# DC_DC_12V.net
KiCad netlist of a schematic drawn in Altium Designer
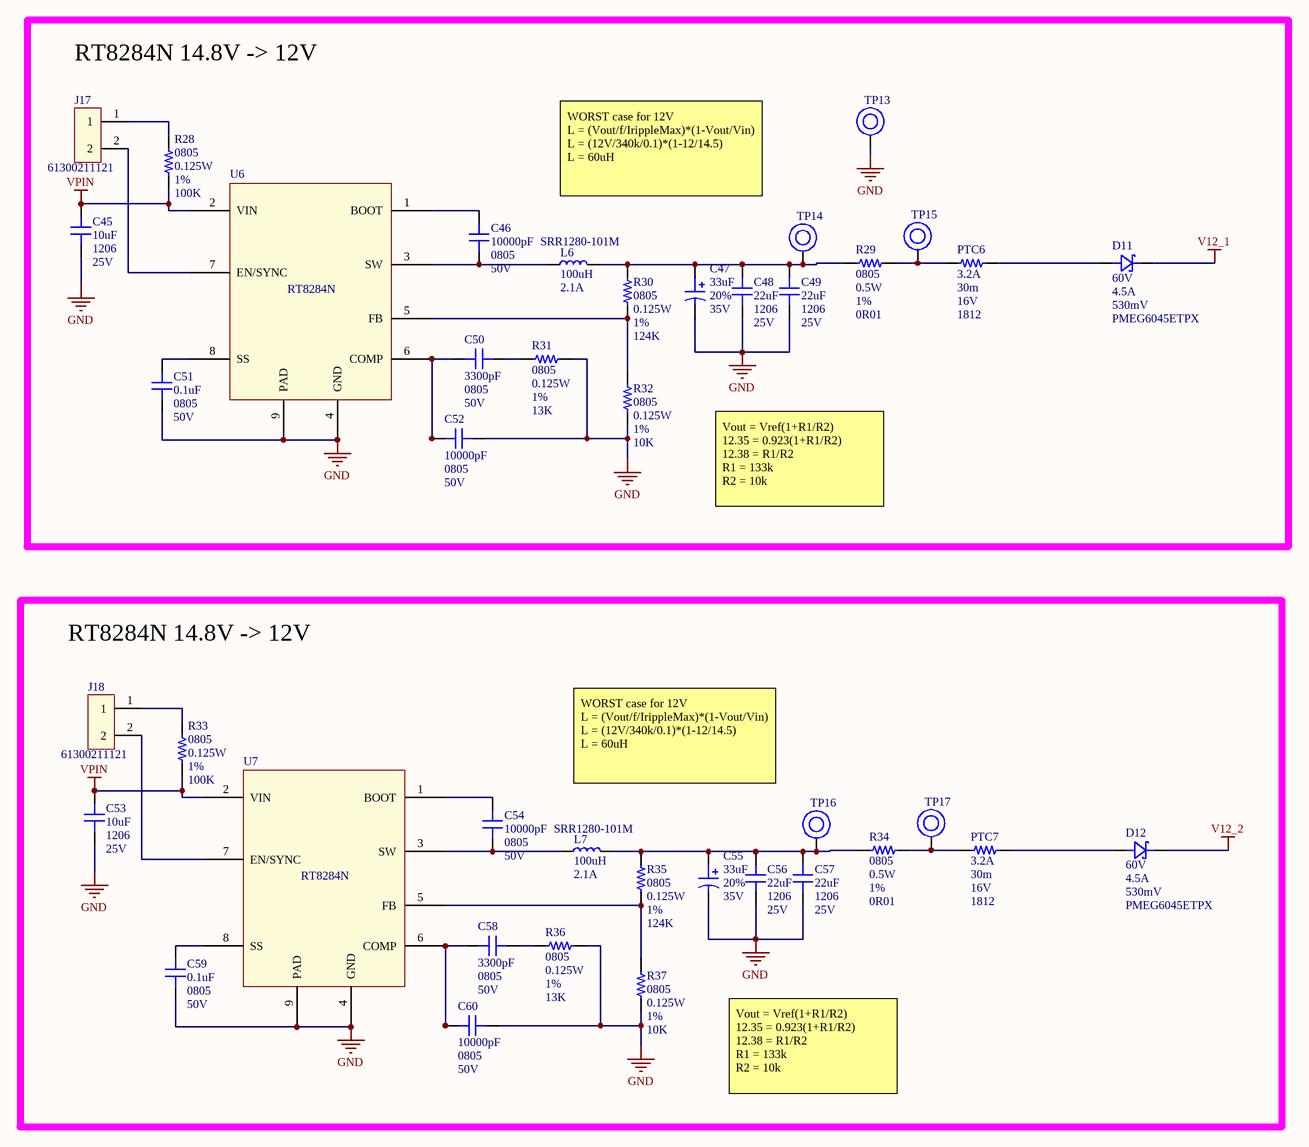
[diagram p0: DC_DC_12V.SchDoc]

(export (version "E")
  (design (tool "Eeschema 10.0.6"))
  (components
    (comp (ref "C45")
      (value "10uF")
      (footprint "CAP_1206")
      (description "CAP CER 10uF 25V 1206")
      (fields
        (field (name "PART NUMBER") "CL31A106KAHNFNE‎")
        (field (name "PACKAGE") "1206")
        (field (name "VOLTAGE") "25V")
        (field (name "Comment") "CAP_‎CL31A106KAHNFNE‎")
      )
      (libsource (lib "SecureBot") (part "CAP_‎CL31A106KAHNFNE‎"))
    )
    (comp (ref "C46")
      (value "10000pF")
      (footprint "CAP_0805")
      (description "CAP CER 10000pF 50V 0805")
      (fields
        (field (name "PART NUMBER") "‎CL21B103KBANNNC")
        (field (name "PACKAGE") "0805")
        (field (name "VOLTAGE") "50V")
        (field (name "Comment") "CAP_‎‎‎‎CL21B103KBANNNC")
      )
      (libsource (lib "SecureBot") (part "CAP_‎‎‎‎CL21B103KBANNNC"))
    )
    (comp (ref "C47")
      (value "33uF")
      (footprint "CAP ALU - 6.3mm DIA")
      (description "CAP ALU 33µF 35V")
      (fields
        (field (name "PART NUMBER") "EEE-FK1V330P")
        (field (name "TOLERANCE") "20%")
        (field (name "VOLTAGE") "35V")
        (field (name "Comment") "CAP_EEE-FK1V330P")
      )
      (libsource (lib "SecureBot") (part "CAP_EEE-FK1V330P"))
    )
    (comp (ref "C48")
      (value "22uF")
      (footprint "CAP_1206")
      (description "CAP CER 22uF 25V 1206")
      (fields
        (field (name "PART NUMBER") "CL31A226KAHNNNE‎")
        (field (name "PACKAGE") "1206")
        (field (name "VOLTAGE") "25V")
        (field (name "Comment") "CAP_‎‎CL31A226KAHNNNE‎")
      )
      (libsource (lib "SecureBot") (part "CAP_‎‎CL31A226KAHNNNE‎"))
    )
    (comp (ref "C49")
      (value "22uF")
      (footprint "CAP_1206")
      (description "CAP CER 22uF 25V 1206")
      (fields
        (field (name "PART NUMBER") "CL31A226KAHNNNE‎")
        (field (name "PACKAGE") "1206")
        (field (name "VOLTAGE") "25V")
        (field (name "Comment") "CAP_‎‎CL31A226KAHNNNE‎")
      )
      (libsource (lib "SecureBot") (part "CAP_‎‎CL31A226KAHNNNE‎"))
    )
    (comp (ref "C50")
      (value "3300pF")
      (footprint "CAP_0805")
      (description "CAP CER 3300pF 50V 0805")
      (fields
        (field (name "PART NUMBER") "CL21B332KBANNNC‎")
        (field (name "PACKAGE") "0805")
        (field (name "VOLTAGE") "50V")
        (field (name "Comment") "CAP_CL21B332KBANNNC‎")
      )
      (libsource (lib "SecureBot") (part "CAP_CL21B332KBANNNC‎"))
    )
    (comp (ref "C51")
      (value "0.1uF")
      (footprint "CAP_0805")
      (description "CAP CER 0.1uF 50V 0805")
      (fields
        (field (name "PART NUMBER") "CC0805KRX7R9BB104‎")
        (field (name "PACKAGE") "0805")
        (field (name "VOLTAGE") "50V")
        (field (name "Comment") "CAP_CC0805KRX7R9BB104‎")
      )
      (libsource (lib "SecureBot") (part "CAP_CC0805KRX7R9BB104‎"))
    )
    (comp (ref "C52")
      (value "10000pF")
      (footprint "CAP_0805")
      (description "CAP CER 10000pF 50V 0805")
      (fields
        (field (name "PART NUMBER") "‎CL21B103KBANNNC")
        (field (name "PACKAGE") "0805")
        (field (name "VOLTAGE") "50V")
        (field (name "Comment") "CAP_‎‎‎‎CL21B103KBANNNC")
      )
      (libsource (lib "SecureBot") (part "CAP_‎‎‎‎CL21B103KBANNNC"))
    )
    (comp (ref "C53")
      (value "10uF")
      (footprint "CAP_1206")
      (description "CAP CER 10uF 25V 1206")
      (fields
        (field (name "PART NUMBER") "CL31A106KAHNFNE‎")
        (field (name "PACKAGE") "1206")
        (field (name "VOLTAGE") "25V")
        (field (name "Comment") "CAP_‎CL31A106KAHNFNE‎")
      )
      (libsource (lib "SecureBot") (part "CAP_‎CL31A106KAHNFNE‎"))
    )
    (comp (ref "C54")
      (value "10000pF")
      (footprint "CAP_0805")
      (description "CAP CER 10000pF 50V 0805")
      (fields
        (field (name "PART NUMBER") "‎CL21B103KBANNNC")
        (field (name "PACKAGE") "0805")
        (field (name "VOLTAGE") "50V")
        (field (name "Comment") "CAP_‎‎‎‎CL21B103KBANNNC")
      )
      (libsource (lib "SecureBot") (part "CAP_‎‎‎‎CL21B103KBANNNC"))
    )
    (comp (ref "C55")
      (value "33uF")
      (footprint "CAP ALU - 6.3mm DIA")
      (description "CAP ALU 33µF 35V")
      (fields
        (field (name "PART NUMBER") "EEE-FK1V330P")
        (field (name "TOLERANCE") "20%")
        (field (name "VOLTAGE") "35V")
        (field (name "Comment") "CAP_EEE-FK1V330P")
      )
      (libsource (lib "SecureBot") (part "CAP_EEE-FK1V330P"))
    )
    (comp (ref "C56")
      (value "22uF")
      (footprint "CAP_1206")
      (description "CAP CER 22uF 25V 1206")
      (fields
        (field (name "PART NUMBER") "CL31A226KAHNNNE‎")
        (field (name "PACKAGE") "1206")
        (field (name "VOLTAGE") "25V")
        (field (name "Comment") "CAP_‎‎CL31A226KAHNNNE‎")
      )
      (libsource (lib "SecureBot") (part "CAP_‎‎CL31A226KAHNNNE‎"))
    )
    (comp (ref "C57")
      (value "22uF")
      (footprint "CAP_1206")
      (description "CAP CER 22uF 25V 1206")
      (fields
        (field (name "PART NUMBER") "CL31A226KAHNNNE‎")
        (field (name "PACKAGE") "1206")
        (field (name "VOLTAGE") "25V")
        (field (name "Comment") "CAP_‎‎CL31A226KAHNNNE‎")
      )
      (libsource (lib "SecureBot") (part "CAP_‎‎CL31A226KAHNNNE‎"))
    )
    (comp (ref "C58")
      (value "3300pF")
      (footprint "CAP_0805")
      (description "CAP CER 3300pF 50V 0805")
      (fields
        (field (name "PART NUMBER") "CL21B332KBANNNC‎")
        (field (name "PACKAGE") "0805")
        (field (name "VOLTAGE") "50V")
        (field (name "Comment") "CAP_CL21B332KBANNNC‎")
      )
      (libsource (lib "SecureBot") (part "CAP_CL21B332KBANNNC‎"))
    )
    (comp (ref "C59")
      (value "0.1uF")
      (footprint "CAP_0805")
      (description "CAP CER 0.1uF 50V 0805")
      (fields
        (field (name "PART NUMBER") "CC0805KRX7R9BB104‎")
        (field (name "PACKAGE") "0805")
        (field (name "VOLTAGE") "50V")
        (field (name "Comment") "CAP_CC0805KRX7R9BB104‎")
      )
      (libsource (lib "SecureBot") (part "CAP_CC0805KRX7R9BB104‎"))
    )
    (comp (ref "C60")
      (value "10000pF")
      (footprint "CAP_0805")
      (description "CAP CER 10000pF 50V 0805")
      (fields
        (field (name "PART NUMBER") "‎CL21B103KBANNNC")
        (field (name "PACKAGE") "0805")
        (field (name "VOLTAGE") "50V")
        (field (name "Comment") "CAP_‎‎‎‎CL21B103KBANNNC")
      )
      (libsource (lib "SecureBot") (part "CAP_‎‎‎‎CL21B103KBANNNC"))
    )
    (comp (ref "D11")
      (value "DIODE_SCH_PMEG6045ETPX")
      (footprint "DO-214AC_SOD128")
      (description "Diode Schottky 60V 4.5A Surface Mount CFP5")
      (fields
        (field (name "VOLTAGE") "60V")
        (field (name "CURRENT") "4.5A")
        (field (name "VF") "530mV")
        (field (name "PART NUMBER") "PMEG6045ETPX")
      )
      (libsource (lib "SecureBot") (part "DIODE_SCH_PMEG6045ETPX"))
    )
    (comp (ref "D12")
      (value "DIODE_SCH_PMEG6045ETPX")
      (footprint "DO-214AC_SOD128")
      (description "Diode Schottky 60V 4.5A Surface Mount CFP5")
      (fields
        (field (name "VOLTAGE") "60V")
        (field (name "CURRENT") "4.5A")
        (field (name "VF") "530mV")
        (field (name "PART NUMBER") "PMEG6045ETPX")
      )
      (libsource (lib "SecureBot") (part "DIODE_SCH_PMEG6045ETPX"))
    )
    (comp (ref "J17")
      (value "Header 2 pin SM")
      (footprint "HDR1X2")
      (fields (field (name "PART NUMBER") "61300211121"))
      (libsource (lib "SecureBot") (part "Header 2 pin SM"))
    )
    (comp (ref "J18")
      (value "Header 2 pin SM")
      (footprint "HDR1X2")
      (fields (field (name "PART NUMBER") "61300211121"))
      (libsource (lib "SecureBot") (part "Header 2 pin SM"))
    )
    (comp (ref "L6")
      (value "100uH")
      (footprint "BOURNS 12.5x12.5mm")
      (description "IND 100µH Shielded Wirewound Inductor 2.1A")
      (fields
        (field (name "TOLERANCE") "20%")
        (field (name "CURRENT") "2.1A")
        (field (name "PART NUMBER") "SRR1280-101M")
        (field (name "Comment") "IND_SRR1280-101M")
      )
      (libsource (lib "SecureBot") (part "IND_SRR1280-101M"))
    )
    (comp (ref "L7")
      (value "100uH")
      (footprint "BOURNS 12.5x12.5mm")
      (description "IND 100µH Shielded Wirewound Inductor 2.1A")
      (fields
        (field (name "TOLERANCE") "20%")
        (field (name "CURRENT") "2.1A")
        (field (name "PART NUMBER") "SRR1280-101M")
        (field (name "Comment") "IND_SRR1280-101M")
      )
      (libsource (lib "SecureBot") (part "IND_SRR1280-101M"))
    )
    (comp (ref "PTC6")
      (value "PTC_0ZCG0160BF2C")
      (footprint "PTC - 1812")
      (description "PTC_Polymeric PTC Resettable Fuse 16V 1.6A Ih")
      (fields
        (field (name "PART NUMBER") "0ZCG0160BF2C")
        (field (name "TRIP VALUE") "3.2A")
        (field (name "RES") "30m")
        (field (name "VOLTAGE") "16V")
        (field (name "PACKAGE") "1812")
      )
      (libsource (lib "SecureBot") (part "PTC_0ZCG0160BF2C"))
    )
    (comp (ref "PTC7")
      (value "PTC_0ZCG0160BF2C")
      (footprint "PTC - 1812")
      (description "PTC_Polymeric PTC Resettable Fuse 16V 1.6A Ih")
      (fields
        (field (name "PART NUMBER") "0ZCG0160BF2C")
        (field (name "TRIP VALUE") "3.2A")
        (field (name "RES") "30m")
        (field (name "VOLTAGE") "16V")
        (field (name "PACKAGE") "1812")
      )
      (libsource (lib "SecureBot") (part "PTC_0ZCG0160BF2C"))
    )
    (comp (ref "R28")
      (value "100K")
      (footprint "RES_0805")
      (description "RES 100K 1% 1/8W 0805")
      (fields
        (field (name "PART NUMBER") "‎RMCF0805FT100K‎")
        (field (name "PACKAGE") "0805")
        (field (name "POWER") "0.125W")
        (field (name "TOLERANCE") "1%")
        (field (name "Comment") "RES_‎RMCF0805FT100K‎")
      )
      (libsource (lib "SecureBot") (part "RES_‎RMCF0805FT100K‎"))
    )
    (comp (ref "R29")
      (value "0R01")
      (footprint "RES_0805")
      (description "RES 0.01R 1% 1/2W 0805")
      (fields
        (field (name "PART NUMBER") "KRL1220E-M-R010-F-T5")
        (field (name "PACKAGE") "0805")
        (field (name "POWER") "0.5W")
        (field (name "TOLERANCE") "1%")
        (field (name "Comment") "RES_‎‎‎‎‎ KRL1220E-M-R010-F-T5")
      )
      (libsource (lib "SecureBot") (part "RES_‎‎‎‎‎ KRL1220E-M-R010-F-T5"))
    )
    (comp (ref "R30")
      (value "124K")
      (footprint "RES_0805")
      (description "RES 124K 1% 1/8W 0805")
      (fields
        (field (name "PART NUMBER") "RMCF0805FT124K")
        (field (name "PACKAGE") "0805")
        (field (name "POWER") "0.125W")
        (field (name "TOLERANCE") "1%")
        (field (name "Comment") "RES_‎RMCF0805FT124K")
      )
      (libsource (lib "SecureBot") (part "RES_‎RMCF0805FT124K"))
    )
    (comp (ref "R31")
      (value "13K")
      (footprint "RES_0805")
      (description "RES 13K 1% 1/8W 0805")
      (fields
        (field (name "PART NUMBER") "RC0805FR-0713KL")
        (field (name "PACKAGE") "0805")
        (field (name "POWER") "0.125W")
        (field (name "TOLERANCE") "1%")
        (field (name "Comment") "RES_‎ RC0805FR-0713KL")
      )
      (libsource (lib "SecureBot") (part "RES_‎ RC0805FR-0713KL"))
    )
    (comp (ref "R32")
      (value "10K")
      (footprint "RES_0805")
      (description "RES 10K 1% 1/8W 0805")
      (fields
        (field (name "PART NUMBER") "RMCF0805FT10K0")
        (field (name "PACKAGE") "0805")
        (field (name "POWER") "0.125W")
        (field (name "TOLERANCE") "1%")
        (field (name "Comment") "RES_‎RMCF0805FT10K0")
      )
      (libsource (lib "SecureBot") (part "RES_‎RMCF0805FT10K0"))
    )
    (comp (ref "R33")
      (value "100K")
      (footprint "RES_0805")
      (description "RES 100K 1% 1/8W 0805")
      (fields
        (field (name "PART NUMBER") "‎RMCF0805FT100K‎")
        (field (name "PACKAGE") "0805")
        (field (name "POWER") "0.125W")
        (field (name "TOLERANCE") "1%")
        (field (name "Comment") "RES_‎RMCF0805FT100K‎")
      )
      (libsource (lib "SecureBot") (part "RES_‎RMCF0805FT100K‎"))
    )
    (comp (ref "R34")
      (value "0R01")
      (footprint "RES_0805")
      (description "RES 0.01R 1% 1/2W 0805")
      (fields
        (field (name "PART NUMBER") "KRL1220E-M-R010-F-T5")
        (field (name "PACKAGE") "0805")
        (field (name "POWER") "0.5W")
        (field (name "TOLERANCE") "1%")
        (field (name "Comment") "RES_‎‎‎‎‎ KRL1220E-M-R010-F-T5")
      )
      (libsource (lib "SecureBot") (part "RES_‎‎‎‎‎ KRL1220E-M-R010-F-T5"))
    )
    (comp (ref "R35")
      (value "124K")
      (footprint "RES_0805")
      (description "RES 124K 1% 1/8W 0805")
      (fields
        (field (name "PART NUMBER") "RMCF0805FT124K")
        (field (name "PACKAGE") "0805")
        (field (name "POWER") "0.125W")
        (field (name "TOLERANCE") "1%")
        (field (name "Comment") "RES_‎RMCF0805FT124K")
      )
      (libsource (lib "SecureBot") (part "RES_‎RMCF0805FT124K"))
    )
    (comp (ref "R36")
      (value "13K")
      (footprint "RES_0805")
      (description "RES 13K 1% 1/8W 0805")
      (fields
        (field (name "PART NUMBER") "RC0805FR-0713KL")
        (field (name "PACKAGE") "0805")
        (field (name "POWER") "0.125W")
        (field (name "TOLERANCE") "1%")
        (field (name "Comment") "RES_‎ RC0805FR-0713KL")
      )
      (libsource (lib "SecureBot") (part "RES_‎ RC0805FR-0713KL"))
    )
    (comp (ref "R37")
      (value "10K")
      (footprint "RES_0805")
      (description "RES 10K 1% 1/8W 0805")
      (fields
        (field (name "PART NUMBER") "RMCF0805FT10K0")
        (field (name "PACKAGE") "0805")
        (field (name "POWER") "0.125W")
        (field (name "TOLERANCE") "1%")
        (field (name "Comment") "RES_‎RMCF0805FT10K0")
      )
      (libsource (lib "SecureBot") (part "RES_‎RMCF0805FT10K0"))
    )
    (comp (ref "TP13")
      (value "TestPoint 3x3mm")
      (footprint "TestPoint 3X3mm")
      (libsource (lib "SecureBot") (part "TestPoint 3x3mm"))
    )
    (comp (ref "TP14")
      (value "TestPoint 3x3mm")
      (footprint "TestPoint 3X3mm")
      (libsource (lib "SecureBot") (part "TestPoint 3x3mm"))
    )
    (comp (ref "TP15")
      (value "TestPoint 3x3mm")
      (footprint "TestPoint 3X3mm")
      (libsource (lib "SecureBot") (part "TestPoint 3x3mm"))
    )
    (comp (ref "TP16")
      (value "TestPoint 3x3mm")
      (footprint "TestPoint 3X3mm")
      (libsource (lib "SecureBot") (part "TestPoint 3x3mm"))
    )
    (comp (ref "TP17")
      (value "TestPoint 3x3mm")
      (footprint "TestPoint 3X3mm")
      (libsource (lib "SecureBot") (part "TestPoint 3x3mm"))
    )
    (comp (ref "U6")
      (value "REG_SW_RT8284N")
      (footprint "SOP8")
      (description "REG 2A, 23V, 340kHz Synchronous Step-Down Converter")
      (fields (field (name "PART NUMBER") "RT8284N"))
      (libsource (lib "SecureBot") (part "REG_SW_RT8284N"))
    )
    (comp (ref "U7")
      (value "REG_SW_RT8284N")
      (footprint "SOP8")
      (description "REG 2A, 23V, 340kHz Synchronous Step-Down Converter")
      (fields (field (name "PART NUMBER") "RT8284N"))
      (libsource (lib "SecureBot") (part "REG_SW_RT8284N"))
    )
  )
  (nets
    (net (code "1") (name "GND") (class "Default")
      (node (ref "C45") (pin "2") (pinfunction "2_2") (pintype "passive"))
      (node (ref "C47") (pin "2") (pinfunction "2_2") (pintype "passive"))
      (node (ref "C48") (pin "2") (pinfunction "2_2") (pintype "passive"))
      (node (ref "C49") (pin "2") (pinfunction "2_2") (pintype "passive"))
      (node (ref "C51") (pin "2") (pinfunction "2_2") (pintype "passive"))
      (node (ref "C52") (pin "2") (pinfunction "2_2") (pintype "passive"))
      (node (ref "C53") (pin "2") (pinfunction "2_2") (pintype "passive"))
      (node (ref "C55") (pin "2") (pinfunction "2_2") (pintype "passive"))
      (node (ref "C56") (pin "2") (pinfunction "2_2") (pintype "passive"))
      (node (ref "C57") (pin "2") (pinfunction "2_2") (pintype "passive"))
      (node (ref "C59") (pin "2") (pinfunction "2_2") (pintype "passive"))
      (node (ref "C60") (pin "2") (pinfunction "2_2") (pintype "passive"))
      (node (ref "R31") (pin "1") (pinfunction "1_1") (pintype "passive"))
      (node (ref "R32") (pin "2") (pinfunction "2_2") (pintype "passive"))
      (node (ref "R36") (pin "1") (pinfunction "1_1") (pintype "passive"))
      (node (ref "R37") (pin "2") (pinfunction "2_2") (pintype "passive"))
      (node (ref "TP13") (pin "1") (pinfunction "1_1") (pintype "passive"))
      (node (ref "U6") (pin "4") (pinfunction "GND_4") (pintype "passive"))
      (node (ref "U6") (pin "9") (pinfunction "PAD_9") (pintype "passive"))
      (node (ref "U7") (pin "4") (pinfunction "GND_4") (pintype "passive"))
      (node (ref "U7") (pin "9") (pinfunction "PAD_9") (pintype "passive"))
    )
    (net (code "2") (name "Net-(C47-Pad1)") (class "Default")
      (node (ref "C47") (pin "1") (pinfunction "1_1") (pintype "passive"))
      (node (ref "C48") (pin "1") (pinfunction "1_1") (pintype "passive"))
      (node (ref "C49") (pin "1") (pinfunction "1_1") (pintype "passive"))
      (node (ref "L6") (pin "2") (pinfunction "2_2") (pintype "passive"))
      (node (ref "R29") (pin "1") (pinfunction "1_1") (pintype "passive"))
      (node (ref "R30") (pin "1") (pinfunction "1_1") (pintype "passive"))
      (node (ref "TP14") (pin "1") (pinfunction "1_1") (pintype "passive"))
    )
    (net (code "3") (name "Net-(C50-Pad2)") (class "Default")
      (node (ref "C50") (pin "2") (pinfunction "2_2") (pintype "passive"))
      (node (ref "R31") (pin "2") (pinfunction "2_2") (pintype "passive"))
    )
    (net (code "4") (name "Net-(C55-Pad1)") (class "Default")
      (node (ref "C55") (pin "1") (pinfunction "1_1") (pintype "passive"))
      (node (ref "C56") (pin "1") (pinfunction "1_1") (pintype "passive"))
      (node (ref "C57") (pin "1") (pinfunction "1_1") (pintype "passive"))
      (node (ref "L7") (pin "2") (pinfunction "2_2") (pintype "passive"))
      (node (ref "R34") (pin "1") (pinfunction "1_1") (pintype "passive"))
      (node (ref "R35") (pin "1") (pinfunction "1_1") (pintype "passive"))
      (node (ref "TP16") (pin "1") (pinfunction "1_1") (pintype "passive"))
    )
    (net (code "5") (name "Net-(C58-Pad2)") (class "Default")
      (node (ref "C58") (pin "2") (pinfunction "2_2") (pintype "passive"))
      (node (ref "R36") (pin "2") (pinfunction "2_2") (pintype "passive"))
    )
    (net (code "6") (name "Net-(D11-Pad1)") (class "Default")
      (node (ref "D11") (pin "1") (pinfunction "1_1") (pintype "passive"))
      (node (ref "PTC6") (pin "2") (pinfunction "2_2") (pintype "passive"))
    )
    (net (code "7") (name "Net-(D12-Pad1)") (class "Default")
      (node (ref "D12") (pin "1") (pinfunction "1_1") (pintype "passive"))
      (node (ref "PTC7") (pin "2") (pinfunction "2_2") (pintype "passive"))
    )
    (net (code "8") (name "Net-(J17-Pad1)") (class "Default")
      (node (ref "J17") (pin "1") (pinfunction "1_1") (pintype "passive"))
      (node (ref "R28") (pin "1") (pinfunction "1_1") (pintype "passive"))
    )
    (net (code "9") (name "Net-(J18-Pad1)") (class "Default")
      (node (ref "J18") (pin "1") (pinfunction "1_1") (pintype "passive"))
      (node (ref "R33") (pin "1") (pinfunction "1_1") (pintype "passive"))
    )
    (net (code "10") (name "Net-(PTC6-Pad1)") (class "Default")
      (node (ref "PTC6") (pin "1") (pinfunction "1_1") (pintype "passive"))
      (node (ref "R29") (pin "2") (pinfunction "2_2") (pintype "passive"))
      (node (ref "TP15") (pin "1") (pinfunction "1_1") (pintype "passive"))
    )
    (net (code "11") (name "Net-(PTC7-Pad1)") (class "Default")
      (node (ref "PTC7") (pin "1") (pinfunction "1_1") (pintype "passive"))
      (node (ref "R34") (pin "2") (pinfunction "2_2") (pintype "passive"))
      (node (ref "TP17") (pin "1") (pinfunction "1_1") (pintype "passive"))
    )
    (net (code "12") (name "Net-(U6-BOOT)") (class "Default")
      (node (ref "C46") (pin "1") (pinfunction "1_1") (pintype "passive"))
      (node (ref "U6") (pin "1") (pinfunction "BOOT_1") (pintype "passive"))
    )
    (net (code "13") (name "Net-(U6-COMP)") (class "Default")
      (node (ref "C50") (pin "1") (pinfunction "1_1") (pintype "passive"))
      (node (ref "C52") (pin "1") (pinfunction "1_1") (pintype "passive"))
      (node (ref "U6") (pin "6") (pinfunction "COMP_6") (pintype "passive"))
    )
    (net (code "14") (name "Net-(U6-EN{slash}SYNC)") (class "Default")
      (node (ref "J17") (pin "2") (pinfunction "2_2") (pintype "passive"))
      (node (ref "U6") (pin "7") (pinfunction "EN/SYNC_7") (pintype "passive"))
    )
    (net (code "15") (name "Net-(U6-FB)") (class "Default")
      (node (ref "R30") (pin "2") (pinfunction "2_2") (pintype "passive"))
      (node (ref "R32") (pin "1") (pinfunction "1_1") (pintype "passive"))
      (node (ref "U6") (pin "5") (pinfunction "FB_5") (pintype "passive"))
    )
    (net (code "16") (name "Net-(U6-SS)") (class "Default")
      (node (ref "C51") (pin "1") (pinfunction "1_1") (pintype "passive"))
      (node (ref "U6") (pin "8") (pinfunction "SS_8") (pintype "passive"))
    )
    (net (code "17") (name "Net-(U6-SW)") (class "Default")
      (node (ref "C46") (pin "2") (pinfunction "2_2") (pintype "passive"))
      (node (ref "L6") (pin "1") (pinfunction "1_1") (pintype "passive"))
      (node (ref "U6") (pin "3") (pinfunction "SW_3") (pintype "passive"))
    )
    (net (code "18") (name "Net-(U7-BOOT)") (class "Default")
      (node (ref "C54") (pin "1") (pinfunction "1_1") (pintype "passive"))
      (node (ref "U7") (pin "1") (pinfunction "BOOT_1") (pintype "passive"))
    )
    (net (code "19") (name "Net-(U7-COMP)") (class "Default")
      (node (ref "C58") (pin "1") (pinfunction "1_1") (pintype "passive"))
      (node (ref "C60") (pin "1") (pinfunction "1_1") (pintype "passive"))
      (node (ref "U7") (pin "6") (pinfunction "COMP_6") (pintype "passive"))
    )
    (net (code "20") (name "Net-(U7-EN{slash}SYNC)") (class "Default")
      (node (ref "J18") (pin "2") (pinfunction "2_2") (pintype "passive"))
      (node (ref "U7") (pin "7") (pinfunction "EN/SYNC_7") (pintype "passive"))
    )
    (net (code "21") (name "Net-(U7-FB)") (class "Default")
      (node (ref "R35") (pin "2") (pinfunction "2_2") (pintype "passive"))
      (node (ref "R37") (pin "1") (pinfunction "1_1") (pintype "passive"))
      (node (ref "U7") (pin "5") (pinfunction "FB_5") (pintype "passive"))
    )
    (net (code "22") (name "Net-(U7-SS)") (class "Default")
      (node (ref "C59") (pin "1") (pinfunction "1_1") (pintype "passive"))
      (node (ref "U7") (pin "8") (pinfunction "SS_8") (pintype "passive"))
    )
    (net (code "23") (name "Net-(U7-SW)") (class "Default")
      (node (ref "C54") (pin "2") (pinfunction "2_2") (pintype "passive"))
      (node (ref "L7") (pin "1") (pinfunction "1_1") (pintype "passive"))
      (node (ref "U7") (pin "3") (pinfunction "SW_3") (pintype "passive"))
    )
    (net (code "24") (name "V12_1") (class "Default")
      (node (ref "D11") (pin "2") (pinfunction "2_2") (pintype "passive"))
    )
    (net (code "25") (name "V12_2") (class "Default")
      (node (ref "D12") (pin "2") (pinfunction "2_2") (pintype "passive"))
    )
    (net (code "26") (name "VPIN") (class "Default")
      (node (ref "C45") (pin "1") (pinfunction "1_1") (pintype "passive"))
      (node (ref "C53") (pin "1") (pinfunction "1_1") (pintype "passive"))
      (node (ref "R28") (pin "2") (pinfunction "2_2") (pintype "passive"))
      (node (ref "R33") (pin "2") (pinfunction "2_2") (pintype "passive"))
      (node (ref "U6") (pin "2") (pinfunction "VIN_2") (pintype "passive"))
      (node (ref "U7") (pin "2") (pinfunction "VIN_2") (pintype "passive"))
    )
  )
)
